# NIXIE_3.net
KiCad netlist of a schematic drawn in Altium Designer
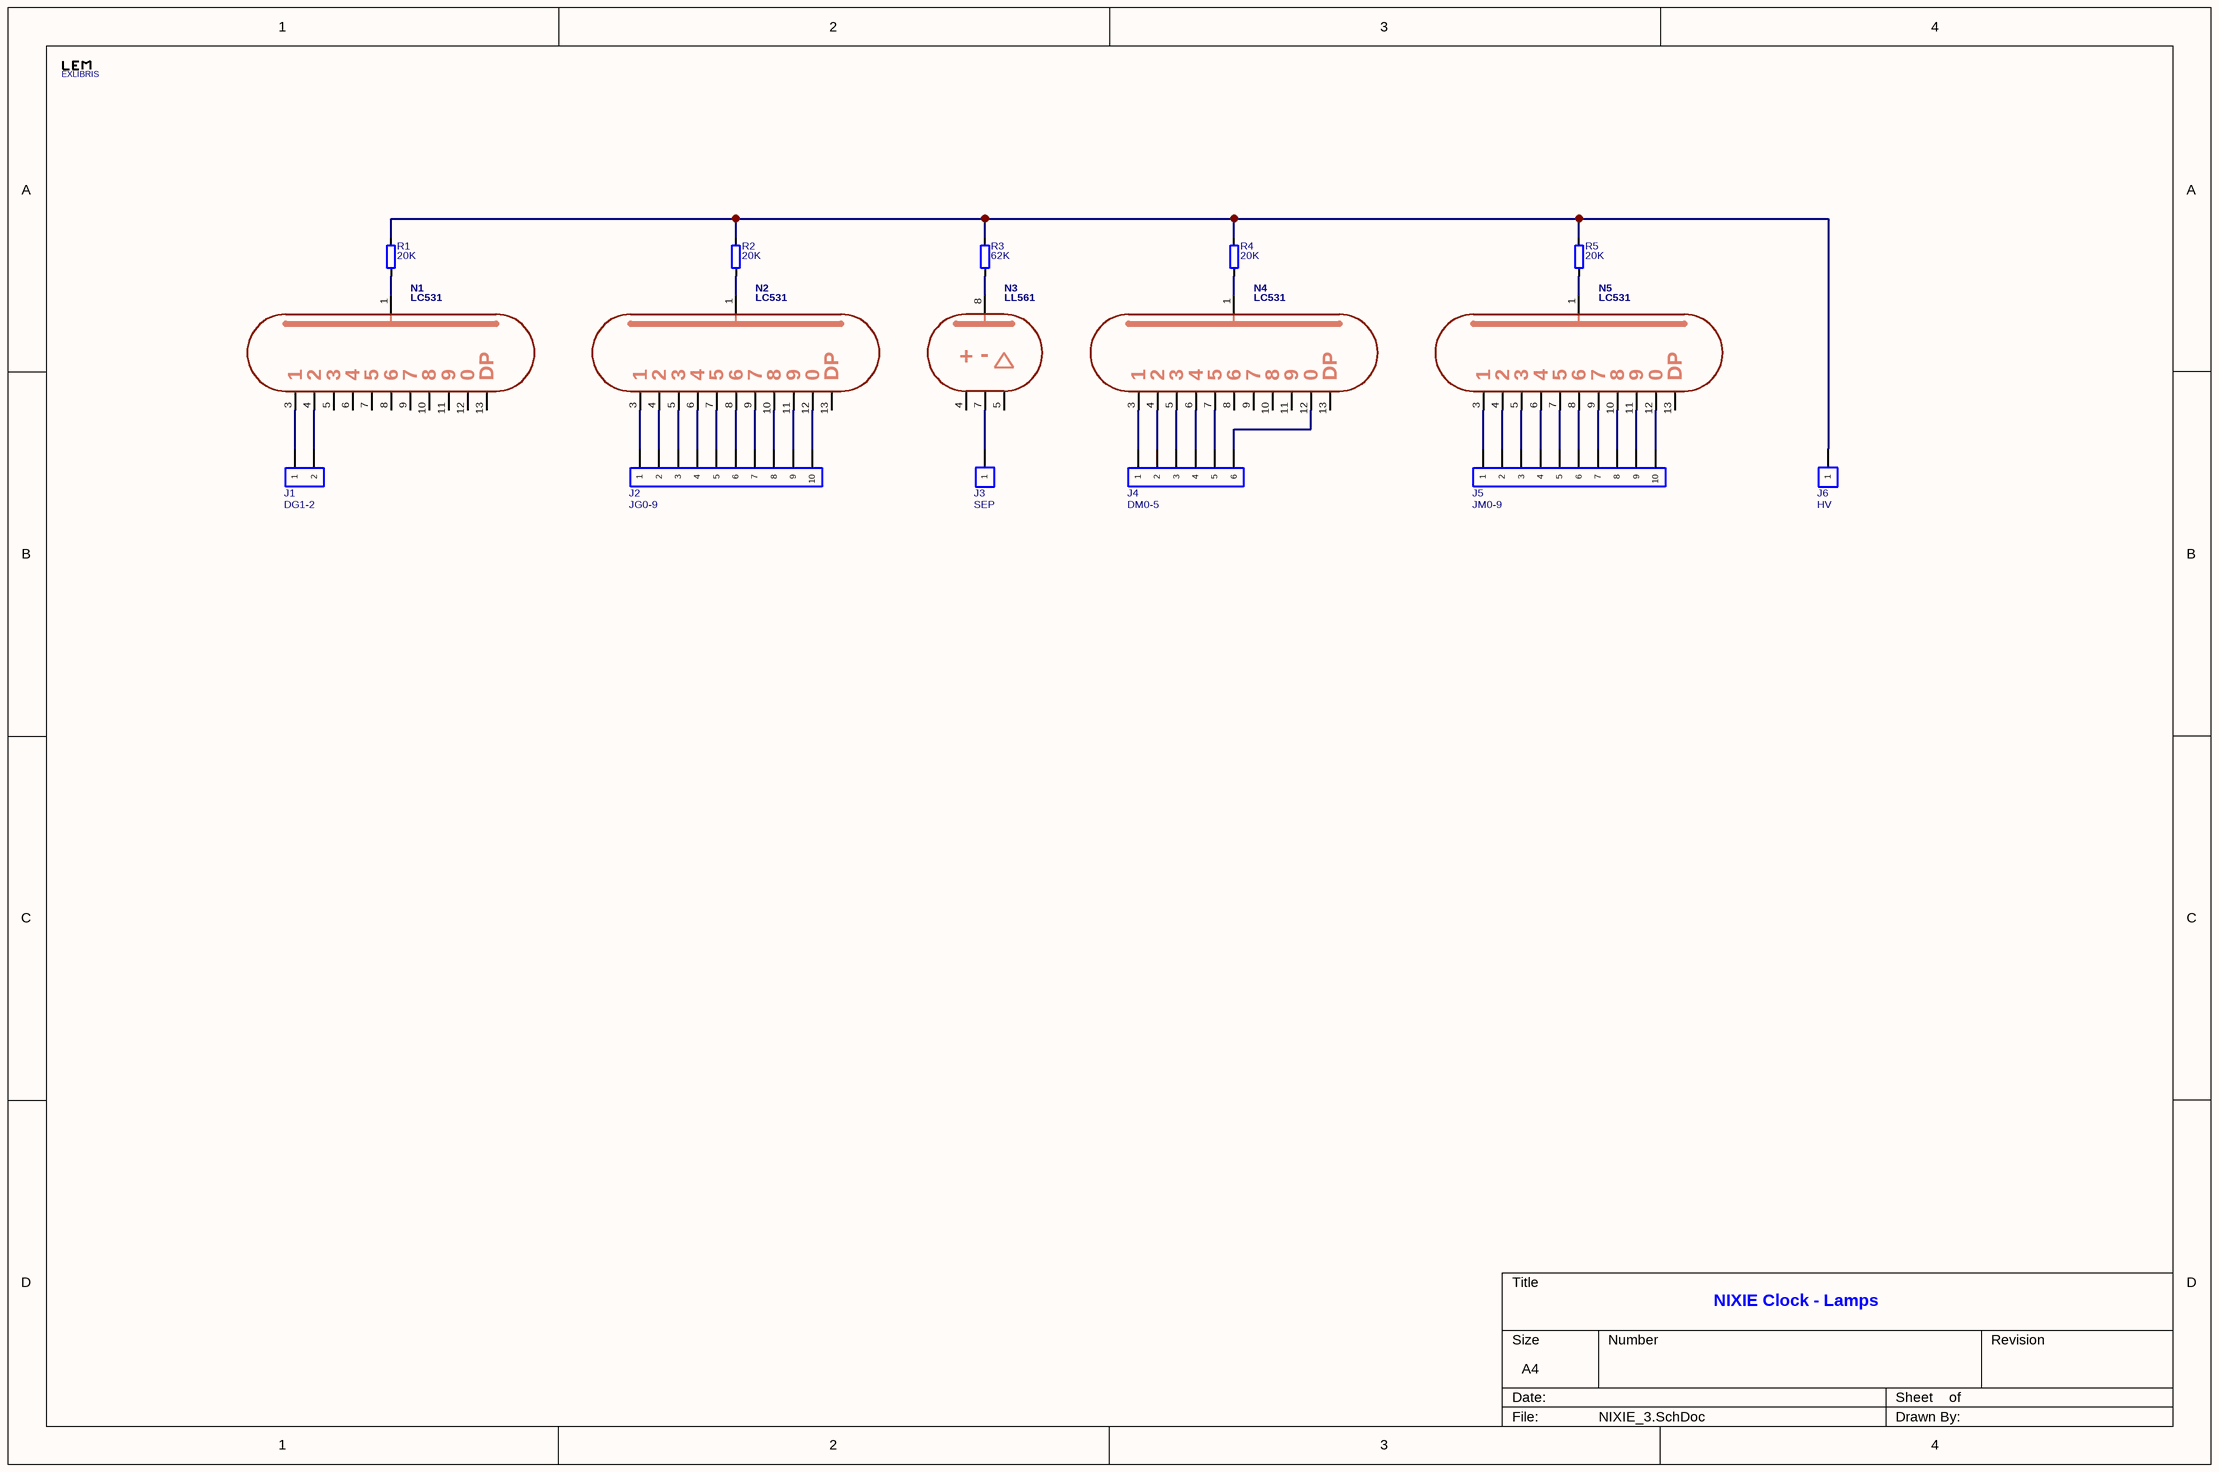
[diagram p0: NIXIE_3.SchDoc]

(export (version "E")
  (design (tool "Eeschema 10.0.6"))
  (components
    (comp (ref "EXLIBRIS") (value "EXLIBRIS") (footprint "EXLBS_2") (libsource (lib "Misc") (part "EXLBR")))
    (comp (ref "J1")
      (value "DG1-2")
      (footprint "SIL2_GP_V")
      (description "Connector 2pin")
      (libsource (lib "Connectors") (part "CON 2pin"))
    )
    (comp (ref "J2")
      (value "JG0-9")
      (footprint "SIL10")
      (description "Connector 10 pin")
      (libsource (lib "Connectors") (part "CON 10pin"))
    )
    (comp (ref "J3")
      (value "SEP")
      (footprint "SIL1")
      (description "Connector 1pin also mounting hole")
      (libsource (lib "Connectors") (part "CON 1pin"))
    )
    (comp (ref "J4")
      (value "DM0-5")
      (footprint "SIL6_GP_V")
      (description "6 Pin Connector")
      (libsource (lib "Connectors") (part "CON 6pin"))
    )
    (comp (ref "J5")
      (value "JM0-9")
      (footprint "SIL10")
      (description "Connector 10 pin")
      (libsource (lib "Connectors") (part "CON 10pin"))
    )
    (comp (ref "J6")
      (value "HV")
      (footprint "SIL1")
      (description "Connector 1pin also mounting hole")
      (libsource (lib "Connectors") (part "CON 1pin"))
    )
    (comp (ref "N1")
      (value "LC531")
      (footprint "Nixie LC531")
      (description "Lampa Numeryczna Nixie")
      (libsource (lib "Wyswietlacze") (part "NIXIE LC531"))
    )
    (comp (ref "N2")
      (value "LC531")
      (footprint "Nixie LC531")
      (description "Lampa Numeryczna Nixie")
      (libsource (lib "Wyswietlacze") (part "NIXIE LC531"))
    )
    (comp (ref "N3")
      (value "LL561")
      (footprint "NIXIE LL561")
      (description "SIGN NEON LAMP")
      (libsource (lib "Wyswietlacze") (part "NIXIE LL561"))
    )
    (comp (ref "N4")
      (value "LC531")
      (footprint "Nixie LC531")
      (description "Lampa Numeryczna Nixie")
      (libsource (lib "Wyswietlacze") (part "NIXIE LC531"))
    )
    (comp (ref "N5")
      (value "LC531")
      (footprint "Nixie LC531")
      (description "Lampa Numeryczna Nixie")
      (libsource (lib "Wyswietlacze") (part "NIXIE LC531"))
    )
    (comp (ref "R1")
      (value "20K")
      (footprint "SMD_R_0805")
      (description "Resistor")
      (libsource (lib "Res") (part "R"))
    )
    (comp (ref "R2")
      (value "20K")
      (footprint "SMD_R_0805")
      (description "Resistor")
      (libsource (lib "Res") (part "R"))
    )
    (comp (ref "R3")
      (value "62K")
      (footprint "SMD_R_0805")
      (description "Resistor")
      (libsource (lib "Res") (part "R"))
    )
    (comp (ref "R4")
      (value "20K")
      (footprint "SMD_R_0805")
      (description "Resistor")
      (libsource (lib "Res") (part "R"))
    )
    (comp (ref "R5")
      (value "20K")
      (footprint "SMD_R_0805")
      (description "Resistor")
      (libsource (lib "Res") (part "R"))
    )
  )
  (nets
    (net (code "1") (name "Net-(J6-Pad1)") (class "Default")
      (node (ref "J6") (pin "1") (pinfunction "1_1") (pintype "passive"))
      (node (ref "R1") (pin "2") (pinfunction "2_2") (pintype "passive"))
      (node (ref "R2") (pin "2") (pinfunction "2_2") (pintype "passive"))
      (node (ref "R3") (pin "2") (pinfunction "2_2") (pintype "passive"))
      (node (ref "R4") (pin "2") (pinfunction "2_2") (pintype "passive"))
      (node (ref "R5") (pin "2") (pinfunction "2_2") (pintype "passive"))
    )
    (net (code "2") (name "Net-(N1-1)") (class "Default")
      (node (ref "J1") (pin "1") (pinfunction "1_1") (pintype "passive"))
      (node (ref "N1") (pin "3") (pinfunction "1_3") (pintype "passive"))
    )
    (net (code "3") (name "Net-(N1-2)") (class "Default")
      (node (ref "J1") (pin "2") (pinfunction "2_2") (pintype "passive"))
      (node (ref "N1") (pin "4") (pinfunction "2_4") (pintype "passive"))
    )
    (net (code "4") (name "Net-(N1-A)") (class "Default")
      (node (ref "N1") (pin "1") (pinfunction "A_1") (pintype "passive"))
      (node (ref "R1") (pin "1") (pinfunction "1_1") (pintype "passive"))
    )
    (net (code "5") (name "Net-(N2-0)") (class "Default")
      (node (ref "J2") (pin "10") (pinfunction "10_10") (pintype "passive"))
      (node (ref "N2") (pin "12") (pinfunction "0_12") (pintype "passive"))
    )
    (net (code "6") (name "Net-(N2-1)") (class "Default")
      (node (ref "J2") (pin "1") (pinfunction "1_1") (pintype "passive"))
      (node (ref "N2") (pin "3") (pinfunction "1_3") (pintype "passive"))
    )
    (net (code "7") (name "Net-(N2-2)") (class "Default")
      (node (ref "J2") (pin "2") (pinfunction "2_2") (pintype "passive"))
      (node (ref "N2") (pin "4") (pinfunction "2_4") (pintype "passive"))
    )
    (net (code "8") (name "Net-(N2-3)") (class "Default")
      (node (ref "J2") (pin "3") (pinfunction "3_3") (pintype "passive"))
      (node (ref "N2") (pin "5") (pinfunction "3_5") (pintype "passive"))
    )
    (net (code "9") (name "Net-(N2-4)") (class "Default")
      (node (ref "J2") (pin "4") (pinfunction "4_4") (pintype "passive"))
      (node (ref "N2") (pin "6") (pinfunction "4_6") (pintype "passive"))
    )
    (net (code "10") (name "Net-(N2-5)") (class "Default")
      (node (ref "J2") (pin "5") (pinfunction "5_5") (pintype "passive"))
      (node (ref "N2") (pin "7") (pinfunction "5_7") (pintype "passive"))
    )
    (net (code "11") (name "Net-(N2-6)") (class "Default")
      (node (ref "J2") (pin "6") (pinfunction "6_6") (pintype "passive"))
      (node (ref "N2") (pin "8") (pinfunction "6_8") (pintype "passive"))
    )
    (net (code "12") (name "Net-(N2-7)") (class "Default")
      (node (ref "J2") (pin "7") (pinfunction "7_7") (pintype "passive"))
      (node (ref "N2") (pin "9") (pinfunction "7_9") (pintype "passive"))
    )
    (net (code "13") (name "Net-(N2-8)") (class "Default")
      (node (ref "J2") (pin "8") (pinfunction "8_8") (pintype "passive"))
      (node (ref "N2") (pin "10") (pinfunction "8_10") (pintype "passive"))
    )
    (net (code "14") (name "Net-(N2-9)") (class "Default")
      (node (ref "J2") (pin "9") (pinfunction "9_9") (pintype "passive"))
      (node (ref "N2") (pin "11") (pinfunction "9_11") (pintype "passive"))
    )
    (net (code "15") (name "Net-(N2-A)") (class "Default")
      (node (ref "N2") (pin "1") (pinfunction "A_1") (pintype "passive"))
      (node (ref "R2") (pin "1") (pinfunction "1_1") (pintype "passive"))
    )
    (net (code "16") (name "Net-(N3--)") (class "Default")
      (node (ref "J3") (pin "1") (pinfunction "1_1") (pintype "passive"))
      (node (ref "N3") (pin "7") (pinfunction "-_7") (pintype "passive"))
    )
    (net (code "17") (name "Net-(N3-A)") (class "Default")
      (node (ref "N3") (pin "8") (pinfunction "A_8") (pintype "passive"))
      (node (ref "R3") (pin "1") (pinfunction "1_1") (pintype "passive"))
    )
    (net (code "18") (name "Net-(N4-0)") (class "Default")
      (node (ref "J4") (pin "6") (pinfunction "6_6") (pintype "passive"))
      (node (ref "N4") (pin "12") (pinfunction "0_12") (pintype "passive"))
    )
    (net (code "19") (name "Net-(N4-1)") (class "Default")
      (node (ref "J4") (pin "1") (pinfunction "1_1") (pintype "passive"))
      (node (ref "N4") (pin "3") (pinfunction "1_3") (pintype "passive"))
    )
    (net (code "20") (name "Net-(N4-2)") (class "Default")
      (node (ref "J4") (pin "2") (pinfunction "2_2") (pintype "passive"))
      (node (ref "N4") (pin "4") (pinfunction "2_4") (pintype "passive"))
    )
    (net (code "21") (name "Net-(N4-3)") (class "Default")
      (node (ref "J4") (pin "3") (pinfunction "3_3") (pintype "passive"))
      (node (ref "N4") (pin "5") (pinfunction "3_5") (pintype "passive"))
    )
    (net (code "22") (name "Net-(N4-4)") (class "Default")
      (node (ref "J4") (pin "4") (pinfunction "4_4") (pintype "passive"))
      (node (ref "N4") (pin "6") (pinfunction "4_6") (pintype "passive"))
    )
    (net (code "23") (name "Net-(N4-5)") (class "Default")
      (node (ref "J4") (pin "5") (pinfunction "5_5") (pintype "passive"))
      (node (ref "N4") (pin "7") (pinfunction "5_7") (pintype "passive"))
    )
    (net (code "24") (name "Net-(N4-A)") (class "Default")
      (node (ref "N4") (pin "1") (pinfunction "A_1") (pintype "passive"))
      (node (ref "R4") (pin "1") (pinfunction "1_1") (pintype "passive"))
    )
    (net (code "25") (name "Net-(N5-0)") (class "Default")
      (node (ref "J5") (pin "10") (pinfunction "10_10") (pintype "passive"))
      (node (ref "N5") (pin "12") (pinfunction "0_12") (pintype "passive"))
    )
    (net (code "26") (name "Net-(N5-1)") (class "Default")
      (node (ref "J5") (pin "1") (pinfunction "1_1") (pintype "passive"))
      (node (ref "N5") (pin "3") (pinfunction "1_3") (pintype "passive"))
    )
    (net (code "27") (name "Net-(N5-2)") (class "Default")
      (node (ref "J5") (pin "2") (pinfunction "2_2") (pintype "passive"))
      (node (ref "N5") (pin "4") (pinfunction "2_4") (pintype "passive"))
    )
    (net (code "28") (name "Net-(N5-3)") (class "Default")
      (node (ref "J5") (pin "3") (pinfunction "3_3") (pintype "passive"))
      (node (ref "N5") (pin "5") (pinfunction "3_5") (pintype "passive"))
    )
    (net (code "29") (name "Net-(N5-4)") (class "Default")
      (node (ref "J5") (pin "4") (pinfunction "4_4") (pintype "passive"))
      (node (ref "N5") (pin "6") (pinfunction "4_6") (pintype "passive"))
    )
    (net (code "30") (name "Net-(N5-5)") (class "Default")
      (node (ref "J5") (pin "5") (pinfunction "5_5") (pintype "passive"))
      (node (ref "N5") (pin "7") (pinfunction "5_7") (pintype "passive"))
    )
    (net (code "31") (name "Net-(N5-6)") (class "Default")
      (node (ref "J5") (pin "6") (pinfunction "6_6") (pintype "passive"))
      (node (ref "N5") (pin "8") (pinfunction "6_8") (pintype "passive"))
    )
    (net (code "32") (name "Net-(N5-7)") (class "Default")
      (node (ref "J5") (pin "7") (pinfunction "7_7") (pintype "passive"))
      (node (ref "N5") (pin "9") (pinfunction "7_9") (pintype "passive"))
    )
    (net (code "33") (name "Net-(N5-8)") (class "Default")
      (node (ref "J5") (pin "8") (pinfunction "8_8") (pintype "passive"))
      (node (ref "N5") (pin "10") (pinfunction "8_10") (pintype "passive"))
    )
    (net (code "34") (name "Net-(N5-9)") (class "Default")
      (node (ref "J5") (pin "9") (pinfunction "9_9") (pintype "passive"))
      (node (ref "N5") (pin "11") (pinfunction "9_11") (pintype "passive"))
    )
    (net (code "35") (name "Net-(N5-A)") (class "Default")
      (node (ref "N5") (pin "1") (pinfunction "A_1") (pintype "passive"))
      (node (ref "R5") (pin "1") (pinfunction "1_1") (pintype "passive"))
    )
    (net (code "36") (name "unconnected-(N1-0-Pad12)") (class "Default")
      (node (ref "N1") (pin "12") (pinfunction "0_12") (pintype "passive"))
    )
    (net (code "37") (name "unconnected-(N1-3-Pad5)") (class "Default")
      (node (ref "N1") (pin "5") (pinfunction "3_5") (pintype "passive"))
    )
    (net (code "38") (name "unconnected-(N1-4-Pad6)") (class "Default")
      (node (ref "N1") (pin "6") (pinfunction "4_6") (pintype "passive"))
    )
    (net (code "39") (name "unconnected-(N1-5-Pad7)") (class "Default")
      (node (ref "N1") (pin "7") (pinfunction "5_7") (pintype "passive"))
    )
    (net (code "40") (name "unconnected-(N1-6-Pad8)") (class "Default")
      (node (ref "N1") (pin "8") (pinfunction "6_8") (pintype "passive"))
    )
    (net (code "41") (name "unconnected-(N1-7-Pad9)") (class "Default")
      (node (ref "N1") (pin "9") (pinfunction "7_9") (pintype "passive"))
    )
    (net (code "42") (name "unconnected-(N1-8-Pad10)") (class "Default")
      (node (ref "N1") (pin "10") (pinfunction "8_10") (pintype "passive"))
    )
    (net (code "43") (name "unconnected-(N1-9-Pad11)") (class "Default")
      (node (ref "N1") (pin "11") (pinfunction "9_11") (pintype "passive"))
    )
    (net (code "44") (name "unconnected-(N1-DP-Pad13)") (class "Default")
      (node (ref "N1") (pin "13") (pinfunction "DP_13") (pintype "passive"))
    )
    (net (code "45") (name "unconnected-(N2-DP-Pad13)") (class "Default")
      (node (ref "N2") (pin "13") (pinfunction "DP_13") (pintype "passive"))
    )
    (net (code "46") (name "unconnected-(N3-+-Pad4)") (class "Default")
      (node (ref "N3") (pin "4") (pinfunction "+_4") (pintype "passive"))
    )
    (net (code "47") (name "unconnected-(N3-DELTA-Pad5)") (class "Default")
      (node (ref "N3") (pin "5") (pinfunction "DELTA_5") (pintype "passive"))
    )
    (net (code "48") (name "unconnected-(N4-6-Pad8)") (class "Default")
      (node (ref "N4") (pin "8") (pinfunction "6_8") (pintype "passive"))
    )
    (net (code "49") (name "unconnected-(N4-7-Pad9)") (class "Default")
      (node (ref "N4") (pin "9") (pinfunction "7_9") (pintype "passive"))
    )
    (net (code "50") (name "unconnected-(N4-8-Pad10)") (class "Default")
      (node (ref "N4") (pin "10") (pinfunction "8_10") (pintype "passive"))
    )
    (net (code "51") (name "unconnected-(N4-9-Pad11)") (class "Default")
      (node (ref "N4") (pin "11") (pinfunction "9_11") (pintype "passive"))
    )
    (net (code "52") (name "unconnected-(N4-DP-Pad13)") (class "Default")
      (node (ref "N4") (pin "13") (pinfunction "DP_13") (pintype "passive"))
    )
    (net (code "53") (name "unconnected-(N5-DP-Pad13)") (class "Default")
      (node (ref "N5") (pin "13") (pinfunction "DP_13") (pintype "passive"))
    )
  )
)
